# momav_power.net
KiCad netlist of a schematic drawn in EAGLE
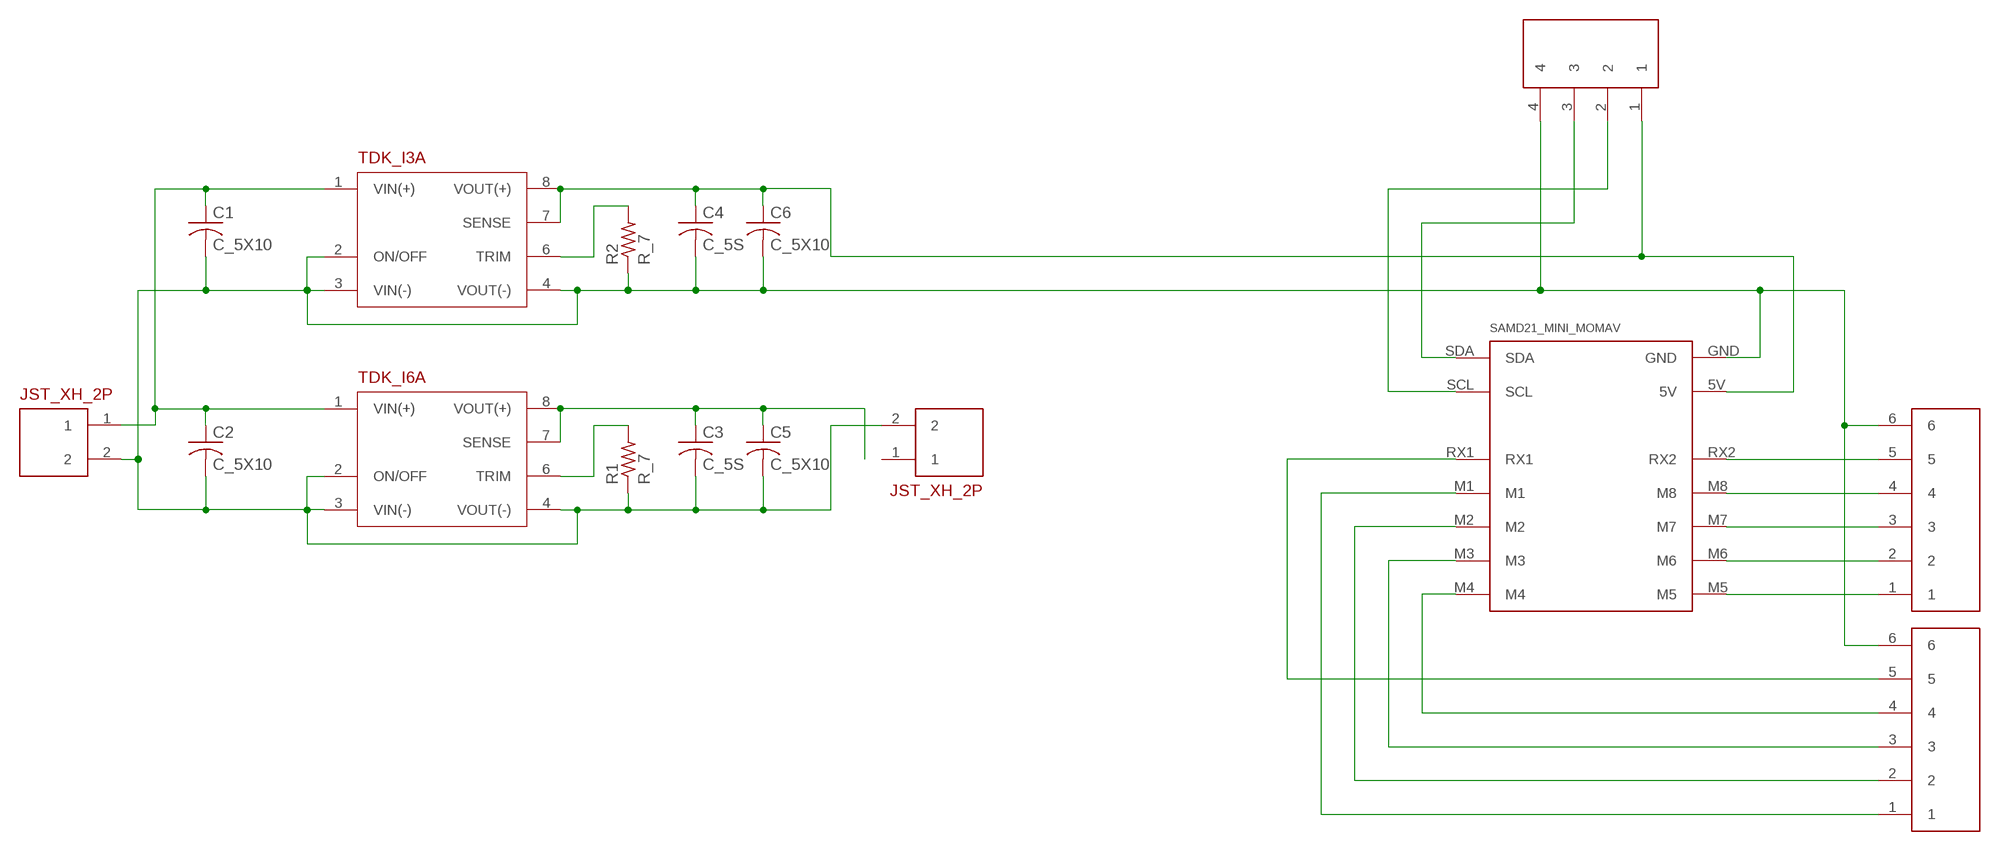
[diagram p0: schematic, sheet 1]

(export (version "E")
  (design (tool "Eeschema 10.0.6"))
  (components
    (comp (ref "C1")
      (value "C_5X10")
      (footprint "eagle-import:C_5X10")
      (libsource (lib "eagle-import") (part "C_5X10"))
    )
    (comp (ref "C2")
      (value "C_5X10")
      (footprint "eagle-import:C_5X10")
      (libsource (lib "eagle-import") (part "C_5X10"))
    )
    (comp (ref "C3")
      (value "C_5S")
      (footprint "eagle-import:C_5S")
      (libsource (lib "eagle-import") (part "C_5S"))
    )
    (comp (ref "C4")
      (value "C_5S")
      (footprint "eagle-import:C_5S")
      (libsource (lib "eagle-import") (part "C_5S"))
    )
    (comp (ref "C5")
      (value "C_5X10")
      (footprint "eagle-import:C_5X10")
      (libsource (lib "eagle-import") (part "C_5X10"))
    )
    (comp (ref "C6")
      (value "C_5X10")
      (footprint "eagle-import:C_5X10")
      (libsource (lib "eagle-import") (part "C_5X10"))
    )
    (comp (ref "R1")
      (value "R_7")
      (footprint "eagle-import:R_7")
      (libsource (lib "eagle-import") (part "R_7"))
    )
    (comp (ref "R2")
      (value "R_7")
      (footprint "eagle-import:R_7")
      (libsource (lib "eagle-import") (part "R_7"))
    )
    (comp (ref "U$1")
      (value "JST_XH_2P")
      (footprint "eagle-import:JST_XH_2P")
      (libsource (lib "eagle-import") (part "JST_XH_2P"))
    )
    (comp (ref "U$2")
      (value "TDK_I3A")
      (footprint "eagle-import:TDK_I3A")
      (libsource (lib "eagle-import") (part "TDK_I3A"))
    )
    (comp (ref "U$3")
      (value "TDK_I6A")
      (footprint "eagle-import:TDK_I6A")
      (libsource (lib "eagle-import") (part "TDK_I6A"))
    )
    (comp (ref "U$4")
      (value "JST_ZH_6P")
      (footprint "eagle-import:JST_ZH_6P")
      (libsource (lib "eagle-import") (part "JST_ZH_6P"))
    )
    (comp (ref "U$5")
      (value "JST_XH_2P")
      (footprint "eagle-import:JST_XH_2P")
      (libsource (lib "eagle-import") (part "JST_XH_2P"))
    )
    (comp (ref "U$6")
      (value "JST_ZH_6P")
      (footprint "eagle-import:JST_ZH_6P")
      (libsource (lib "eagle-import") (part "JST_ZH_6P"))
    )
    (comp (ref "U$7")
      (value "JST_ZH_4P")
      (footprint "eagle-import:JST_ZH_4P")
      (libsource (lib "eagle-import") (part "JST_ZH_4P"))
    )
    (comp (ref "U$8")
      (value "SAMD21_MINI_MOMAV2")
      (footprint "eagle-import:SAMD21_MINI_MOMAV2")
      (libsource (lib "eagle-import") (part "SAMD21_MINI_MOMAV2"))
    )
  )
  (nets
    (net (code "1") (name "Net-(U$2-ON{slash}OFF)") (class "Default")
      (node (ref "C1") (pin "2") (pinfunction "2_2") (pintype "passive"))
      (node (ref "C2") (pin "2") (pinfunction "2_2") (pintype "passive"))
      (node (ref "C3") (pin "2") (pinfunction "2_2") (pintype "passive"))
      (node (ref "C4") (pin "2") (pinfunction "2_2") (pintype "passive"))
      (node (ref "C5") (pin "2") (pinfunction "2_2") (pintype "passive"))
      (node (ref "C6") (pin "2") (pinfunction "2_2") (pintype "passive"))
      (node (ref "R1") (pin "1") (pinfunction "1_1") (pintype "passive"))
      (node (ref "R2") (pin "1") (pinfunction "1_1") (pintype "passive"))
      (node (ref "U$1") (pin "2") (pinfunction "2_2") (pintype "bidirectional"))
      (node (ref "U$2") (pin "2") (pinfunction "ON/OFF_2") (pintype "bidirectional"))
      (node (ref "U$2") (pin "3") (pinfunction "VIN(-)_3") (pintype "bidirectional"))
      (node (ref "U$2") (pin "4") (pinfunction "VOUT(-)_4") (pintype "bidirectional"))
      (node (ref "U$3") (pin "2") (pinfunction "ON/OFF_2") (pintype "bidirectional"))
      (node (ref "U$3") (pin "3") (pinfunction "VIN(-)_3") (pintype "bidirectional"))
      (node (ref "U$3") (pin "4") (pinfunction "VOUT(-)_4") (pintype "bidirectional"))
      (node (ref "U$4") (pin "6") (pinfunction "6_6") (pintype "bidirectional"))
      (node (ref "U$5") (pin "2") (pinfunction "2_2") (pintype "bidirectional"))
      (node (ref "U$6") (pin "6") (pinfunction "6_6") (pintype "bidirectional"))
      (node (ref "U$7") (pin "4") (pinfunction "4_4") (pintype "bidirectional"))
      (node (ref "U$8") (pin "GND") (pinfunction "GND_GND") (pintype "bidirectional"))
    )
    (net (code "2") (name "Net-(U$2-SENSE)") (class "Default")
      (node (ref "C4") (pin "1") (pinfunction "1_1") (pintype "passive"))
      (node (ref "C6") (pin "1") (pinfunction "1_1") (pintype "passive"))
      (node (ref "U$2") (pin "7") (pinfunction "SENSE_7") (pintype "bidirectional"))
      (node (ref "U$2") (pin "8") (pinfunction "VOUT(+)_8") (pintype "bidirectional"))
      (node (ref "U$7") (pin "1") (pinfunction "1_1") (pintype "bidirectional"))
      (node (ref "U$8") (pin "5V") (pinfunction "5V_5V") (pintype "bidirectional"))
    )
    (net (code "3") (name "Net-(U$2-TRIM)") (class "Default")
      (node (ref "R2") (pin "2") (pinfunction "2_2") (pintype "passive"))
      (node (ref "U$2") (pin "6") (pinfunction "TRIM_6") (pintype "bidirectional"))
    )
    (net (code "4") (name "Net-(U$2-VIN(+))") (class "Default")
      (node (ref "C1") (pin "1") (pinfunction "1_1") (pintype "passive"))
      (node (ref "C2") (pin "1") (pinfunction "1_1") (pintype "passive"))
      (node (ref "U$2") (pin "1") (pinfunction "VIN(+)_1") (pintype "bidirectional"))
      (node (ref "U$3") (pin "1") (pinfunction "VIN(+)_1") (pintype "bidirectional"))
      (node (ref "U$5") (pin "1") (pinfunction "1_1") (pintype "bidirectional"))
    )
    (net (code "5") (name "Net-(U$3-SENSE)") (class "Default")
      (node (ref "C3") (pin "1") (pinfunction "1_1") (pintype "passive"))
      (node (ref "C5") (pin "1") (pinfunction "1_1") (pintype "passive"))
      (node (ref "U$3") (pin "7") (pinfunction "SENSE_7") (pintype "bidirectional"))
      (node (ref "U$3") (pin "8") (pinfunction "VOUT(+)_8") (pintype "bidirectional"))
    )
    (net (code "6") (name "Net-(U$3-TRIM)") (class "Default")
      (node (ref "R1") (pin "2") (pinfunction "2_2") (pintype "passive"))
      (node (ref "U$3") (pin "6") (pinfunction "TRIM_6") (pintype "bidirectional"))
    )
    (net (code "7") (name "Net-(U$4-Pad1)") (class "Default")
      (node (ref "U$4") (pin "1") (pinfunction "1_1") (pintype "bidirectional"))
      (node (ref "U$8") (pin "M1") (pinfunction "M1_M1") (pintype "bidirectional"))
    )
    (net (code "8") (name "Net-(U$4-Pad2)") (class "Default")
      (node (ref "U$4") (pin "2") (pinfunction "2_2") (pintype "bidirectional"))
      (node (ref "U$8") (pin "M2") (pinfunction "M2_M2") (pintype "bidirectional"))
    )
    (net (code "9") (name "Net-(U$4-Pad3)") (class "Default")
      (node (ref "U$4") (pin "3") (pinfunction "3_3") (pintype "bidirectional"))
      (node (ref "U$8") (pin "M3") (pinfunction "M3_M3") (pintype "bidirectional"))
    )
    (net (code "10") (name "Net-(U$4-Pad4)") (class "Default")
      (node (ref "U$4") (pin "4") (pinfunction "4_4") (pintype "bidirectional"))
      (node (ref "U$8") (pin "M4") (pinfunction "M4_M4") (pintype "bidirectional"))
    )
    (net (code "11") (name "Net-(U$4-Pad5)") (class "Default")
      (node (ref "U$4") (pin "5") (pinfunction "5_5") (pintype "bidirectional"))
      (node (ref "U$8") (pin "RX1") (pinfunction "RX1_RX1") (pintype "bidirectional"))
    )
    (net (code "12") (name "Net-(U$6-Pad1)") (class "Default")
      (node (ref "U$6") (pin "1") (pinfunction "1_1") (pintype "bidirectional"))
      (node (ref "U$8") (pin "M5") (pinfunction "M5_M5") (pintype "bidirectional"))
    )
    (net (code "13") (name "Net-(U$6-Pad2)") (class "Default")
      (node (ref "U$6") (pin "2") (pinfunction "2_2") (pintype "bidirectional"))
      (node (ref "U$8") (pin "M6") (pinfunction "M6_M6") (pintype "bidirectional"))
    )
    (net (code "14") (name "Net-(U$6-Pad3)") (class "Default")
      (node (ref "U$6") (pin "3") (pinfunction "3_3") (pintype "bidirectional"))
      (node (ref "U$8") (pin "M7") (pinfunction "M7_M7") (pintype "bidirectional"))
    )
    (net (code "15") (name "Net-(U$6-Pad4)") (class "Default")
      (node (ref "U$6") (pin "4") (pinfunction "4_4") (pintype "bidirectional"))
      (node (ref "U$8") (pin "M8") (pinfunction "M8_M8") (pintype "bidirectional"))
    )
    (net (code "16") (name "Net-(U$6-Pad5)") (class "Default")
      (node (ref "U$6") (pin "5") (pinfunction "5_5") (pintype "bidirectional"))
      (node (ref "U$8") (pin "RX2") (pinfunction "RX2_RX2") (pintype "bidirectional"))
    )
    (net (code "17") (name "Net-(U$7-Pad2)") (class "Default")
      (node (ref "U$7") (pin "2") (pinfunction "2_2") (pintype "bidirectional"))
      (node (ref "U$8") (pin "SCL") (pinfunction "SCL_SCL") (pintype "bidirectional"))
    )
    (net (code "18") (name "Net-(U$7-Pad3)") (class "Default")
      (node (ref "U$7") (pin "3") (pinfunction "3_3") (pintype "bidirectional"))
      (node (ref "U$8") (pin "SDA") (pinfunction "SDA_SDA") (pintype "bidirectional"))
    )
    (net (code "19") (name "unconnected-(U$1-Pad1)") (class "Default")
      (node (ref "U$1") (pin "1") (pinfunction "1_1") (pintype "bidirectional"))
    )
  )
)
